# Steuerungsmodul.net
KiCad netlist of a schematic drawn in EAGLE
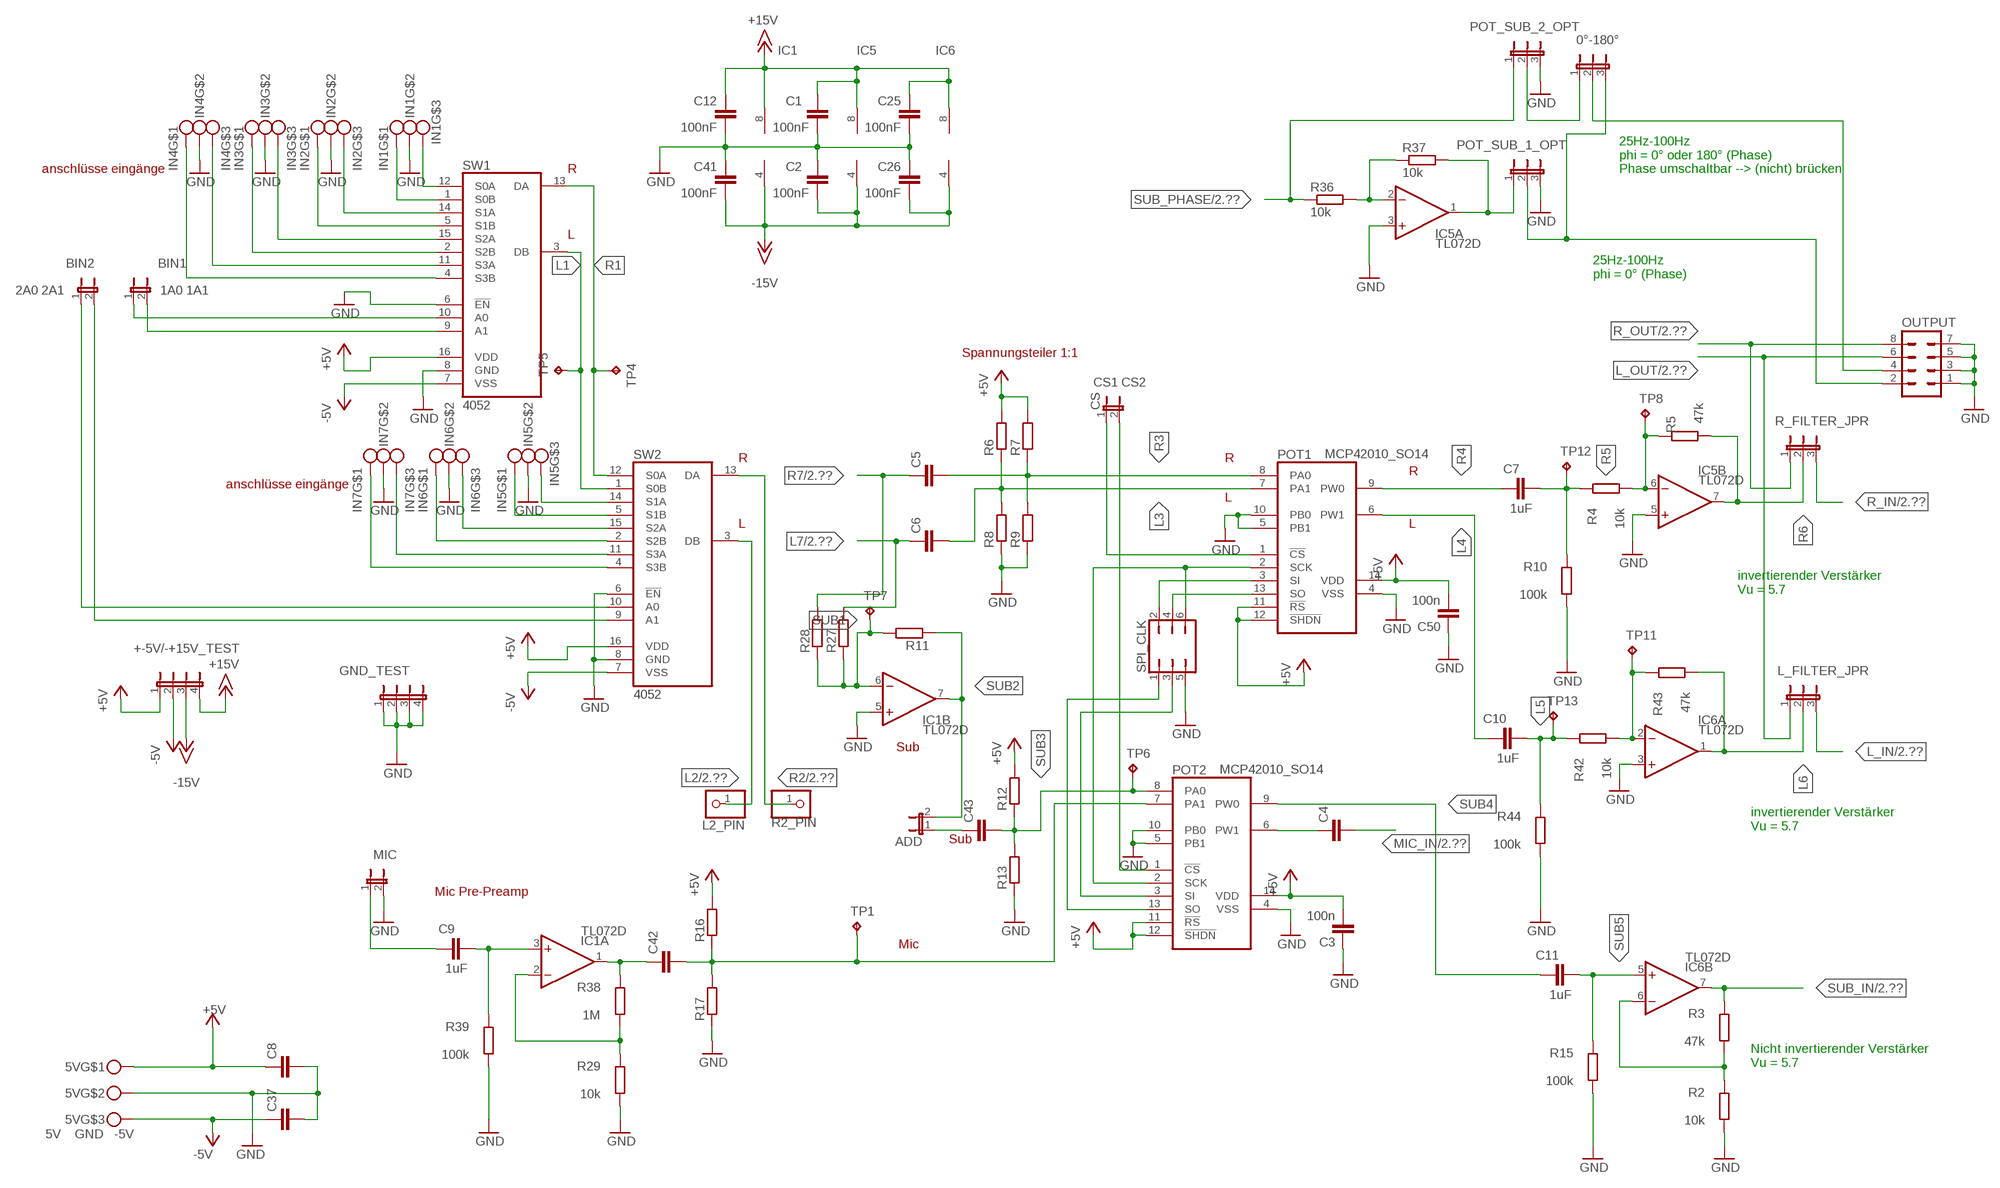
[diagram p0: schematic, sheet 1]
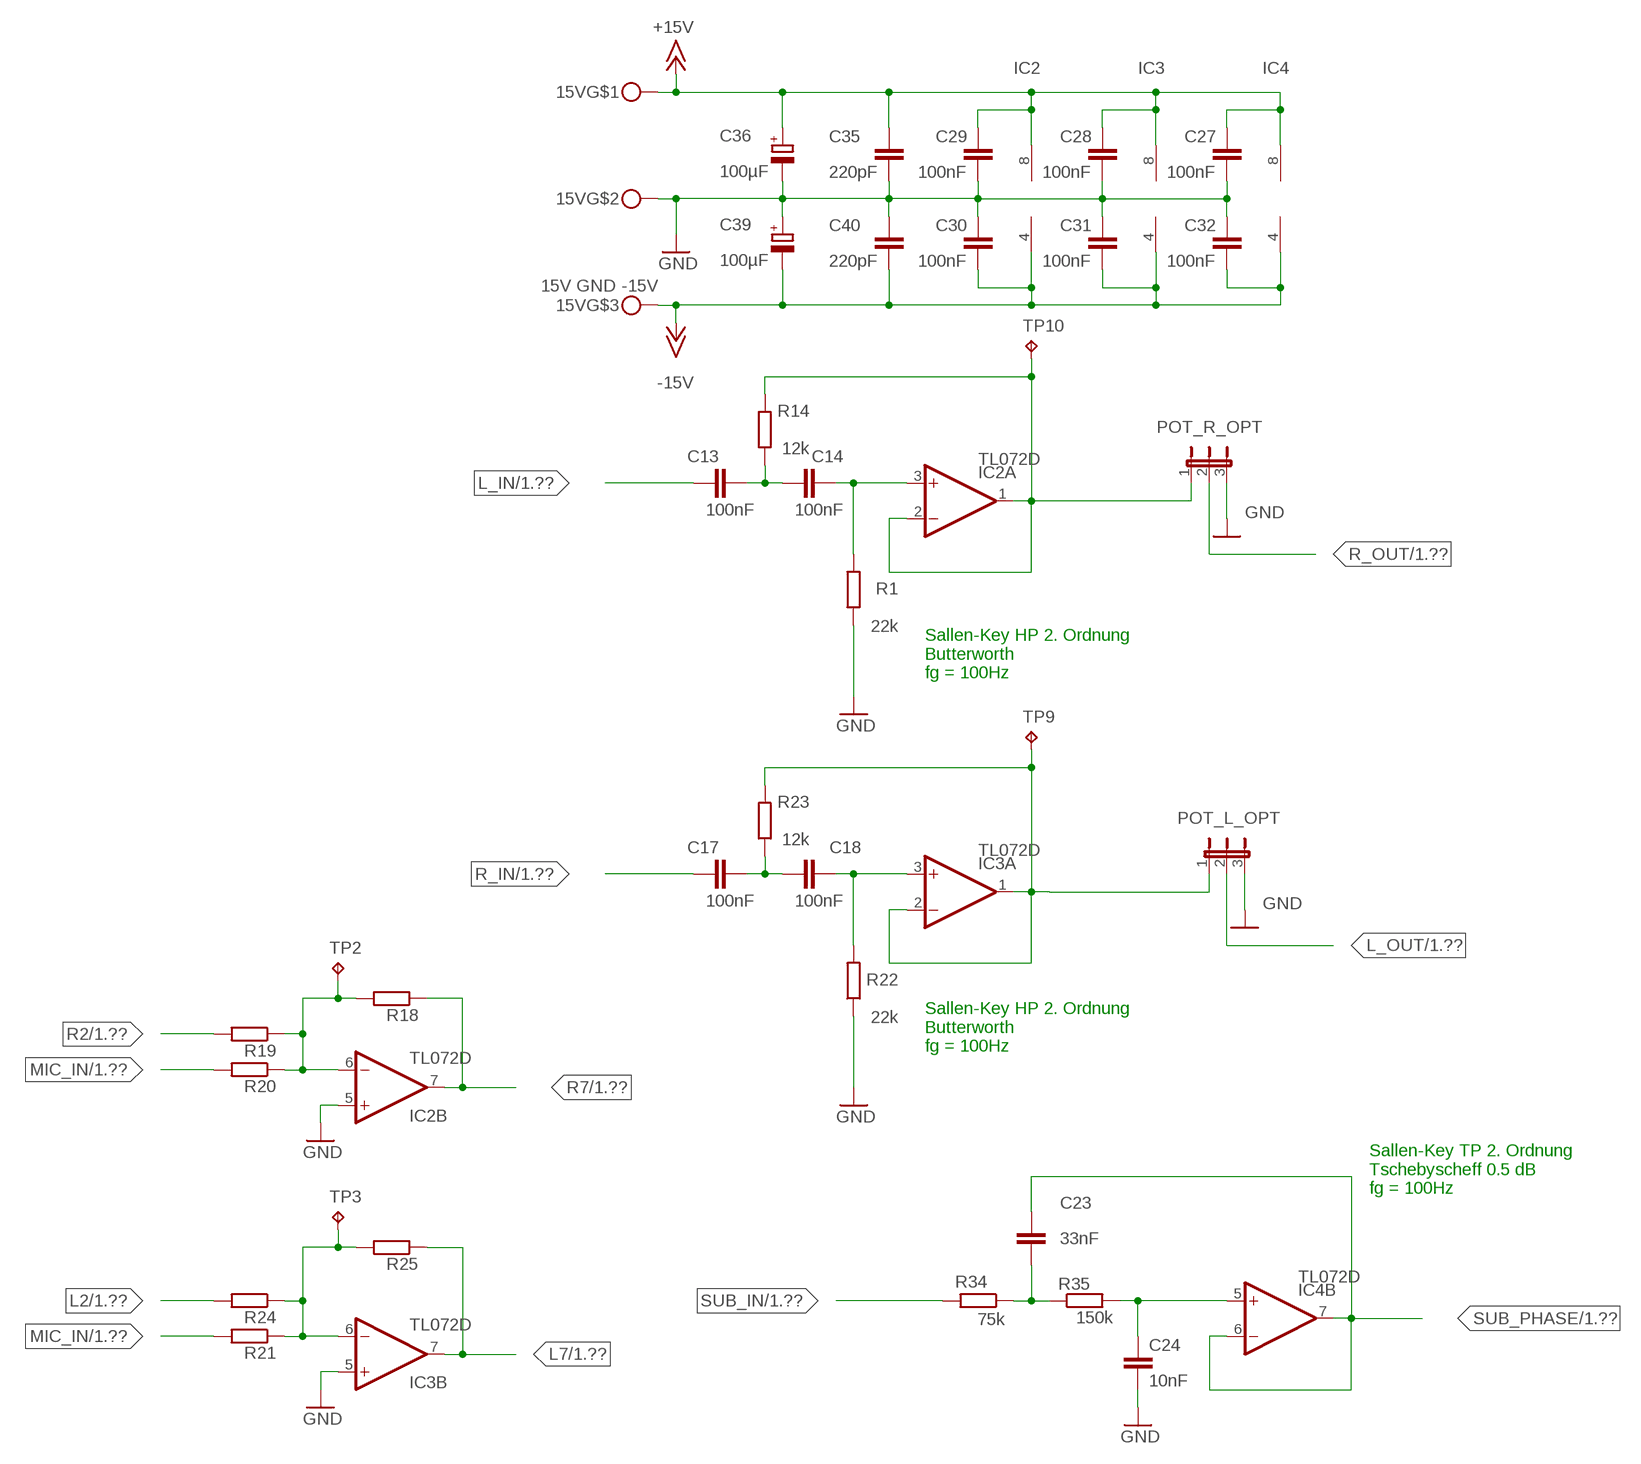
[diagram p1: schematic, sheet 2]

(export (version "E")
  (design (tool "Eeschema 10.0.6"))
  (components
    (comp (ref "+-5V/-+15V_TEST")
      (value "JP4E")
      (footprint "eagle-import:JP4")
      (libsource (lib "eagle-import") (part "JP4E"))
    )
    (comp (ref "0°-180°")
      (value "JMP3")
      (footprint "eagle-import:JMP3")
      (libsource (lib "eagle-import") (part "JMP3"))
    )
    (comp (ref "5V")
      (value "5V GND -5V")
      (footprint "eagle-import:MKDS3_3_5,08")
      (libsource (lib "eagle-import") (part "MKDS3/3_5,08"))
    )
    (comp (ref "ADD")
      (value "JMP2")
      (footprint "eagle-import:JMP2")
      (libsource (lib "eagle-import") (part "JMP2"))
    )
    (comp (ref "BIN1")
      (value "1A0 1A1")
      (footprint "eagle-import:JMP2")
      (libsource (lib "eagle-import") (part "JMP2"))
    )
    (comp (ref "BIN2")
      (value "2A0 2A1")
      (footprint "eagle-import:JMP2")
      (fields (field (name "SPICEPREFIX") "B"))
      (libsource (lib "eagle-import") (part "JMP2"))
    )
    (comp (ref "C1")
      (value "100nF")
      (footprint "eagle-import:C0805")
      (libsource (lib "eagle-import") (part "C-EUC0805"))
    )
    (comp (ref "C2")
      (value "100nF")
      (footprint "eagle-import:C0805")
      (libsource (lib "eagle-import") (part "C-EUC0805"))
    )
    (comp (ref "C3")
      (value "100n")
      (footprint "eagle-import:C0805")
      (libsource (lib "eagle-import") (part "C-EUC0805"))
    )
    (comp (ref "C4")
      (value "C-EUC0805")
      (footprint "eagle-import:C0805")
      (libsource (lib "eagle-import") (part "C-EUC0805"))
    )
    (comp (ref "C5")
      (value "C-EUC0805")
      (footprint "eagle-import:C0805")
      (libsource (lib "eagle-import") (part "C-EUC0805"))
    )
    (comp (ref "C6")
      (value "C-EUC0805")
      (footprint "eagle-import:C0805")
      (libsource (lib "eagle-import") (part "C-EUC0805"))
    )
    (comp (ref "C7")
      (value "1uF")
      (footprint "eagle-import:C025-025X050")
      (libsource (lib "eagle-import") (part "resistor_C-EU025-025X050"))
    )
    (comp (ref "C8")
      (value "C-EUC0805")
      (footprint "eagle-import:C0805")
      (libsource (lib "eagle-import") (part "C-EUC0805"))
    )
    (comp (ref "C9")
      (value "1uF")
      (footprint "eagle-import:C025-025X050")
      (libsource (lib "eagle-import") (part "resistor_C-EU025-025X050"))
    )
    (comp (ref "C10")
      (value "1uF")
      (footprint "eagle-import:C025-025X050")
      (libsource (lib "eagle-import") (part "resistor_C-EU025-025X050"))
    )
    (comp (ref "C11")
      (value "1uF")
      (footprint "eagle-import:C025-025X050")
      (libsource (lib "eagle-import") (part "resistor_C-EU025-025X050"))
    )
    (comp (ref "C12")
      (value "100nF")
      (footprint "eagle-import:C0805")
      (libsource (lib "eagle-import") (part "C-EUC0805"))
    )
    (comp (ref "C25")
      (value "100nF")
      (footprint "eagle-import:C0805")
      (libsource (lib "eagle-import") (part "C-EUC0805"))
    )
    (comp (ref "C26")
      (value "100nF")
      (footprint "eagle-import:C0805")
      (libsource (lib "eagle-import") (part "C-EUC0805"))
    )
    (comp (ref "C37")
      (value "C-EUC0805")
      (footprint "eagle-import:C0805")
      (libsource (lib "eagle-import") (part "C-EUC0805"))
    )
    (comp (ref "C41")
      (value "100nF")
      (footprint "eagle-import:C0805")
      (libsource (lib "eagle-import") (part "C-EUC0805"))
    )
    (comp (ref "C42")
      (value "C-EUC0805")
      (footprint "eagle-import:C0805")
      (libsource (lib "eagle-import") (part "C-EUC0805"))
    )
    (comp (ref "C43")
      (value "C-EUC0805")
      (footprint "eagle-import:C0805")
      (libsource (lib "eagle-import") (part "C-EUC0805"))
    )
    (comp (ref "C50")
      (value "100n")
      (footprint "eagle-import:C0805")
      (libsource (lib "eagle-import") (part "C-EUC0805"))
    )
    (comp (ref "CS")
      (value "CS1 CS2")
      (footprint "eagle-import:JMP2")
      (libsource (lib "eagle-import") (part "JMP2"))
    )
    (comp (ref "GND_TEST")
      (value "JP4E")
      (footprint "eagle-import:JP4")
      (libsource (lib "eagle-import") (part "jumper_252_JP4E"))
    )
    (comp (ref "IC1")
      (value "TL072D")
      (footprint "eagle-import:SO08")
      (libsource (lib "eagle-import") (part "TL072D"))
    )
    (comp (ref "IC5")
      (value "TL072D")
      (footprint "eagle-import:SO08")
      (libsource (lib "eagle-import") (part "TL072D"))
    )
    (comp (ref "IC6")
      (value "TL072D")
      (footprint "eagle-import:SO08")
      (libsource (lib "eagle-import") (part "TL072D"))
    )
    (comp (ref "IN1")
      (value "MKDS3/3_5,08")
      (footprint "eagle-import:MKDS3_3_5,08")
      (libsource (lib "eagle-import") (part "MKDS3/3_5,08"))
    )
    (comp (ref "IN2")
      (value "MKDS3/3_5,08")
      (footprint "eagle-import:MKDS3_3_5,08")
      (libsource (lib "eagle-import") (part "MKDS3/3_5,08"))
    )
    (comp (ref "IN3")
      (value "MKDS3/3_5,08")
      (footprint "eagle-import:MKDS3_3_5,08")
      (libsource (lib "eagle-import") (part "MKDS3/3_5,08"))
    )
    (comp (ref "IN4")
      (value "MKDS3/3_5,08")
      (footprint "eagle-import:MKDS3_3_5,08")
      (libsource (lib "eagle-import") (part "MKDS3/3_5,08"))
    )
    (comp (ref "IN5")
      (value "MKDS3/3_5,08")
      (footprint "eagle-import:MKDS3_3_5,08")
      (libsource (lib "eagle-import") (part "MKDS3/3_5,08"))
    )
    (comp (ref "IN6")
      (value "MKDS3/3_5,08")
      (footprint "eagle-import:MKDS3_3_5,08")
      (libsource (lib "eagle-import") (part "MKDS3/3_5,08"))
    )
    (comp (ref "IN7")
      (value "MKDS3/3_5,08")
      (footprint "eagle-import:MKDS3_3_5,08")
      (libsource (lib "eagle-import") (part "MKDS3/3_5,08"))
    )
    (comp (ref "L2_PIN")
      (value "PINHD-1X1")
      (footprint "eagle-import:1X01")
      (libsource (lib "eagle-import") (part "PINHD-1X1"))
    )
    (comp (ref "L_FILTER_JPR")
      (value "JMP3")
      (footprint "eagle-import:JMP3")
      (libsource (lib "eagle-import") (part "JMP3"))
    )
    (comp (ref "MIC")
      (value "JMP2")
      (footprint "eagle-import:JMP2")
      (libsource (lib "eagle-import") (part "JMP2"))
    )
    (comp (ref "OUTPUT")
      (value "MA04-2")
      (footprint "eagle-import:MA04-2")
      (libsource (lib "eagle-import") (part "MA04-2"))
    )
    (comp (ref "POT1")
      (value "MCP42010_SO14")
      (footprint "eagle-import:SO14")
      (libsource (lib "eagle-import") (part "MCP42010_SO14"))
    )
    (comp (ref "POT2")
      (value "MCP42010_SO14")
      (footprint "eagle-import:SO14")
      (libsource (lib "eagle-import") (part "MCP42010_SO14"))
    )
    (comp (ref "POT_SUB_1_OPT")
      (value "JMP3")
      (footprint "eagle-import:JMP3")
      (libsource (lib "eagle-import") (part "JMP3"))
    )
    (comp (ref "POT_SUB_2_OPT")
      (value "JMP3")
      (footprint "eagle-import:JMP3")
      (libsource (lib "eagle-import") (part "JMP3"))
    )
    (comp (ref "R2")
      (value "10k")
      (footprint "eagle-import:M0805")
      (libsource (lib "eagle-import") (part "R-EU_M0805"))
    )
    (comp (ref "R2_PIN")
      (value "PINHD-1X1")
      (footprint "eagle-import:1X01")
      (libsource (lib "eagle-import") (part "PINHD-1X1"))
    )
    (comp (ref "R3")
      (value "47k")
      (footprint "eagle-import:M0805")
      (libsource (lib "eagle-import") (part "R-EU_M0805"))
    )
    (comp (ref "R4")
      (value "10k")
      (footprint "eagle-import:M0805")
      (libsource (lib "eagle-import") (part "R-EU_M0805"))
    )
    (comp (ref "R5")
      (value "47k")
      (footprint "eagle-import:M0805")
      (libsource (lib "eagle-import") (part "R-EU_M0805"))
    )
    (comp (ref "R6")
      (value "R-EU_M0805")
      (footprint "eagle-import:M0805")
      (libsource (lib "eagle-import") (part "R-EU_M0805"))
    )
    (comp (ref "R7")
      (value "R-EU_M0805")
      (footprint "eagle-import:M0805")
      (libsource (lib "eagle-import") (part "R-EU_M0805"))
    )
    (comp (ref "R8")
      (value "R-EU_M0805")
      (footprint "eagle-import:M0805")
      (libsource (lib "eagle-import") (part "R-EU_M0805"))
    )
    (comp (ref "R9")
      (value "R-EU_M0805")
      (footprint "eagle-import:M0805")
      (libsource (lib "eagle-import") (part "R-EU_M0805"))
    )
    (comp (ref "R10")
      (value "100k")
      (footprint "eagle-import:M0805")
      (libsource (lib "eagle-import") (part "R-EU_M0805"))
    )
    (comp (ref "R11")
      (value "R-EU_M0805")
      (footprint "eagle-import:M0805")
      (libsource (lib "eagle-import") (part "R-EU_M0805"))
    )
    (comp (ref "R12")
      (value "R-EU_M0805")
      (footprint "eagle-import:M0805")
      (libsource (lib "eagle-import") (part "R-EU_M0805"))
    )
    (comp (ref "R13")
      (value "R-EU_M0805")
      (footprint "eagle-import:M0805")
      (libsource (lib "eagle-import") (part "R-EU_M0805"))
    )
    (comp (ref "R15")
      (value "100k")
      (footprint "eagle-import:M0805")
      (libsource (lib "eagle-import") (part "R-EU_M0805"))
    )
    (comp (ref "R16")
      (value "R-EU_M0805")
      (footprint "eagle-import:M0805")
      (libsource (lib "eagle-import") (part "R-EU_M0805"))
    )
    (comp (ref "R17")
      (value "R-EU_M0805")
      (footprint "eagle-import:M0805")
      (libsource (lib "eagle-import") (part "R-EU_M0805"))
    )
    (comp (ref "R27")
      (value "R-EU_M0805")
      (footprint "eagle-import:M0805")
      (libsource (lib "eagle-import") (part "R-EU_M0805"))
    )
    (comp (ref "R28")
      (value "R-EU_M0805")
      (footprint "eagle-import:M0805")
      (libsource (lib "eagle-import") (part "R-EU_M0805"))
    )
    (comp (ref "R29")
      (value "10k")
      (footprint "eagle-import:M0805")
      (libsource (lib "eagle-import") (part "R-EU_M0805"))
    )
    (comp (ref "R36")
      (value "10k")
      (footprint "eagle-import:M0805")
      (libsource (lib "eagle-import") (part "R-EU_M0805"))
    )
    (comp (ref "R37")
      (value "10k")
      (footprint "eagle-import:M0805")
      (libsource (lib "eagle-import") (part "R-EU_M0805"))
    )
    (comp (ref "R38")
      (value "1M")
      (footprint "eagle-import:M0805")
      (libsource (lib "eagle-import") (part "R-EU_M0805"))
    )
    (comp (ref "R39")
      (value "100k")
      (footprint "eagle-import:M0805")
      (libsource (lib "eagle-import") (part "R-EU_M0805"))
    )
    (comp (ref "R42")
      (value "10k")
      (footprint "eagle-import:M0805")
      (libsource (lib "eagle-import") (part "R-EU_M0805"))
    )
    (comp (ref "R43")
      (value "47k")
      (footprint "eagle-import:M0805")
      (libsource (lib "eagle-import") (part "R-EU_M0805"))
    )
    (comp (ref "R44")
      (value "100k")
      (footprint "eagle-import:M0805")
      (libsource (lib "eagle-import") (part "R-EU_M0805"))
    )
    (comp (ref "R_FILTER_JPR")
      (value "JMP3")
      (footprint "eagle-import:JMP3")
      (libsource (lib "eagle-import") (part "JMP3"))
    )
    (comp (ref "SPI_CLK")
      (value "JP3Q")
      (footprint "eagle-import:JP3Q")
      (libsource (lib "eagle-import") (part "JP3Q"))
    )
    (comp (ref "SW1")
      (value "4052")
      (footprint "eagle-import:SO-16")
      (libsource (lib "eagle-import") (part "5042_SO16_NEU"))
    )
    (comp (ref "SW2")
      (value "4052")
      (footprint "eagle-import:SO-16")
      (libsource (lib "eagle-import") (part "5042_SO16_NEU"))
    )
    (comp (ref "TP1")
      (value "TPB2,54")
      (footprint "eagle-import:B2,54")
      (libsource (lib "eagle-import") (part "TPB2,54"))
    )
    (comp (ref "TP4")
      (value "TPB2,54")
      (footprint "eagle-import:B2,54")
      (libsource (lib "eagle-import") (part "TPB2,54"))
    )
    (comp (ref "TP5")
      (value "TPB2,54")
      (footprint "eagle-import:B2,54")
      (libsource (lib "eagle-import") (part "TPB2,54"))
    )
    (comp (ref "TP6")
      (value "TPB2,54")
      (footprint "eagle-import:B2,54")
      (libsource (lib "eagle-import") (part "TPB2,54"))
    )
    (comp (ref "TP7")
      (value "TPB2,54")
      (footprint "eagle-import:B2,54")
      (libsource (lib "eagle-import") (part "TPB2,54"))
    )
    (comp (ref "TP8")
      (value "TPB2,54")
      (footprint "eagle-import:B2,54")
      (libsource (lib "eagle-import") (part "TPB2,54"))
    )
    (comp (ref "TP11")
      (value "TPB2,54")
      (footprint "eagle-import:B2,54")
      (libsource (lib "eagle-import") (part "TPB2,54"))
    )
    (comp (ref "TP12")
      (value "TPB2,54")
      (footprint "eagle-import:B2,54")
      (libsource (lib "eagle-import") (part "TPB2,54"))
    )
    (comp (ref "TP13")
      (value "TPB2,54")
      (footprint "eagle-import:B2,54")
      (libsource (lib "eagle-import") (part "TPB2,54"))
    )
    (comp (ref "15V")
      (value "15V GND -15V")
      (footprint "eagle-import:MKDS3_3_5,08")
      (libsource (lib "eagle-import") (part "MKDS3/3_5,08"))
    )
    (comp (ref "C13")
      (value "100nF")
      (footprint "eagle-import:C0805")
      (libsource (lib "eagle-import") (part "C-EUC0805"))
    )
    (comp (ref "C14")
      (value "100nF")
      (footprint "eagle-import:C0805")
      (libsource (lib "eagle-import") (part "C-EUC0805"))
    )
    (comp (ref "C17")
      (value "100nF")
      (footprint "eagle-import:C0805")
      (libsource (lib "eagle-import") (part "C-EUC0805"))
    )
    (comp (ref "C18")
      (value "100nF")
      (footprint "eagle-import:C0805")
      (libsource (lib "eagle-import") (part "C-EUC0805"))
    )
    (comp (ref "C23")
      (value "33nF")
      (footprint "eagle-import:C0805")
      (libsource (lib "eagle-import") (part "C-EUC0805"))
    )
    (comp (ref "C24")
      (value "10nF")
      (footprint "eagle-import:C0805")
      (libsource (lib "eagle-import") (part "C-EUC0805"))
    )
    (comp (ref "C27")
      (value "100nF")
      (footprint "eagle-import:C0805")
      (libsource (lib "eagle-import") (part "C-EUC0805"))
    )
    (comp (ref "C28")
      (value "100nF")
      (footprint "eagle-import:C0805")
      (libsource (lib "eagle-import") (part "C-EUC0805"))
    )
    (comp (ref "C29")
      (value "100nF")
      (footprint "eagle-import:C0805")
      (libsource (lib "eagle-import") (part "C-EUC0805"))
    )
    (comp (ref "C30")
      (value "100nF")
      (footprint "eagle-import:C0805")
      (libsource (lib "eagle-import") (part "C-EUC0805"))
    )
    (comp (ref "C31")
      (value "100nF")
      (footprint "eagle-import:C0805")
      (libsource (lib "eagle-import") (part "C-EUC0805"))
    )
    (comp (ref "C32")
      (value "100nF")
      (footprint "eagle-import:C0805")
      (libsource (lib "eagle-import") (part "C-EUC0805"))
    )
    (comp (ref "C35")
      (value "220pF")
      (footprint "eagle-import:C0805")
      (libsource (lib "eagle-import") (part "C-EUC0805"))
    )
    (comp (ref "C36")
      (value "100µF")
      (footprint "eagle-import:E2,5-6")
      (libsource (lib "eagle-import") (part "CPOL-EUE2.5-6"))
    )
    (comp (ref "C39")
      (value "100µF")
      (footprint "eagle-import:E2,5-6")
      (libsource (lib "eagle-import") (part "CPOL-EUE2.5-6"))
    )
    (comp (ref "C40")
      (value "220pF")
      (footprint "eagle-import:C0805")
      (libsource (lib "eagle-import") (part "C-EUC0805"))
    )
    (comp (ref "IC2")
      (value "TL072D")
      (footprint "eagle-import:SO08")
      (libsource (lib "eagle-import") (part "TL072D"))
    )
    (comp (ref "IC3")
      (value "TL072D")
      (footprint "eagle-import:SO08")
      (libsource (lib "eagle-import") (part "TL072D"))
    )
    (comp (ref "IC4")
      (value "TL072D")
      (footprint "eagle-import:SO08")
      (libsource (lib "eagle-import") (part "TL072D"))
    )
    (comp (ref "POT_L_OPT")
      (value "JMP3")
      (footprint "eagle-import:JMP3")
      (libsource (lib "eagle-import") (part "JMP3"))
    )
    (comp (ref "POT_R_OPT")
      (value "JMP3")
      (footprint "eagle-import:JMP3")
      (libsource (lib "eagle-import") (part "JMP3"))
    )
    (comp (ref "R1")
      (value "22k")
      (footprint "eagle-import:M0805")
      (libsource (lib "eagle-import") (part "R-EU_M0805"))
    )
    (comp (ref "R14")
      (value "12k")
      (footprint "eagle-import:M0805")
      (libsource (lib "eagle-import") (part "R-EU_M0805"))
    )
    (comp (ref "R18")
      (value "R-EU_M0805")
      (footprint "eagle-import:M0805")
      (libsource (lib "eagle-import") (part "R-EU_M0805"))
    )
    (comp (ref "R19")
      (value "R-EU_M0805")
      (footprint "eagle-import:M0805")
      (libsource (lib "eagle-import") (part "R-EU_M0805"))
    )
    (comp (ref "R20")
      (value "R-EU_M0805")
      (footprint "eagle-import:M0805")
      (libsource (lib "eagle-import") (part "R-EU_M0805"))
    )
    (comp (ref "R21")
      (value "R-EU_M0805")
      (footprint "eagle-import:M0805")
      (libsource (lib "eagle-import") (part "R-EU_M0805"))
    )
    (comp (ref "R22")
      (value "22k")
      (footprint "eagle-import:M0805")
      (libsource (lib "eagle-import") (part "R-EU_M0805"))
    )
    (comp (ref "R23")
      (value "12k")
      (footprint "eagle-import:M0805")
      (libsource (lib "eagle-import") (part "R-EU_M0805"))
    )
    (comp (ref "R24")
      (value "R-EU_M0805")
      (footprint "eagle-import:M0805")
      (libsource (lib "eagle-import") (part "R-EU_M0805"))
    )
    (comp (ref "R25")
      (value "R-EU_M0805")
      (footprint "eagle-import:M0805")
      (libsource (lib "eagle-import") (part "R-EU_M0805"))
    )
    (comp (ref "R34")
      (value "75k")
      (footprint "eagle-import:M0805")
      (libsource (lib "eagle-import") (part "R-EU_M0805"))
    )
    (comp (ref "R35")
      (value "150k")
      (footprint "eagle-import:M0805")
      (libsource (lib "eagle-import") (part "R-EU_M0805"))
    )
    (comp (ref "TP2")
      (value "TPB2,54")
      (footprint "eagle-import:B2,54")
      (libsource (lib "eagle-import") (part "TPB2,54"))
    )
    (comp (ref "TP3")
      (value "TPB2,54")
      (footprint "eagle-import:B2,54")
      (libsource (lib "eagle-import") (part "TPB2,54"))
    )
    (comp (ref "TP9")
      (value "TPB2,54")
      (footprint "eagle-import:B2,54")
      (libsource (lib "eagle-import") (part "TPB2,54"))
    )
    (comp (ref "TP10")
      (value "TPB2,54")
      (footprint "eagle-import:B2,54")
      (libsource (lib "eagle-import") (part "TPB2,54"))
    )
  )
  (nets
    (net (code "1") (name "+5V") (class "Default")
      (node (ref "+-5V/-+15V_TEST") (pin "1") (pinfunction "1_1") (pintype "passive"))
      (node (ref "5V") (pin "P$1") (pinfunction "KL_P$1") (pintype "passive"))
      (node (ref "C3") (pin "2") (pinfunction "2_2") (pintype "passive"))
      (node (ref "C50") (pin "2") (pinfunction "2_2") (pintype "passive"))
      (node (ref "C8") (pin "1") (pinfunction "1_1") (pintype "passive"))
      (node (ref "POT1") (pin "11") (pinfunction "~{RS}_11") (pintype "bidirectional"))
      (node (ref "POT1") (pin "12") (pinfunction "~{SHDN}_12") (pintype "bidirectional"))
      (node (ref "POT1") (pin "14") (pinfunction "VDD_14") (pintype "input"))
      (node (ref "POT2") (pin "11") (pinfunction "~{RS}_11") (pintype "bidirectional"))
      (node (ref "POT2") (pin "12") (pinfunction "~{SHDN}_12") (pintype "bidirectional"))
      (node (ref "POT2") (pin "14") (pinfunction "VDD_14") (pintype "input"))
      (node (ref "R12") (pin "2") (pinfunction "2_2") (pintype "passive"))
      (node (ref "R16") (pin "2") (pinfunction "2_2") (pintype "passive"))
      (node (ref "R6") (pin "2") (pinfunction "2_2") (pintype "passive"))
      (node (ref "R7") (pin "2") (pinfunction "2_2") (pintype "passive"))
      (node (ref "SW1") (pin "16") (pinfunction "VDD_16") (pintype "bidirectional"))
      (node (ref "SW2") (pin "16") (pinfunction "VDD_16") (pintype "bidirectional"))
    )
    (net (code "2") (name "+15V") (class "Default")
      (node (ref "+-5V/-+15V_TEST") (pin "4") (pinfunction "4_4") (pintype "passive"))
      (node (ref "15V") (pin "P$1") (pinfunction "KL_P$1") (pintype "passive"))
      (node (ref "C1") (pin "1") (pinfunction "1_1") (pintype "passive"))
      (node (ref "C12") (pin "1") (pinfunction "1_1") (pintype "passive"))
      (node (ref "C25") (pin "1") (pinfunction "1_1") (pintype "passive"))
      (node (ref "C27") (pin "1") (pinfunction "1_1") (pintype "passive"))
      (node (ref "C28") (pin "1") (pinfunction "1_1") (pintype "passive"))
      (node (ref "C29") (pin "1") (pinfunction "1_1") (pintype "passive"))
      (node (ref "C35") (pin "1") (pinfunction "1_1") (pintype "passive"))
      (node (ref "C36") (pin "+") (pinfunction "+_+") (pintype "passive"))
      (node (ref "IC1") (pin "8") (pinfunction "V+_8") (pintype "power_in"))
      (node (ref "IC2") (pin "8") (pinfunction "V+_8") (pintype "power_in"))
      (node (ref "IC3") (pin "8") (pinfunction "V+_8") (pintype "power_in"))
      (node (ref "IC4") (pin "8") (pinfunction "V+_8") (pintype "power_in"))
      (node (ref "IC5") (pin "8") (pinfunction "V+_8") (pintype "power_in"))
      (node (ref "IC6") (pin "8") (pinfunction "V+_8") (pintype "power_in"))
    )
    (net (code "3") (name "-5V") (class "Default")
      (node (ref "+-5V/-+15V_TEST") (pin "2") (pinfunction "2_2") (pintype "passive"))
      (node (ref "5V") (pin "P$3") (pinfunction "KL_P$3") (pintype "passive"))
      (node (ref "C37") (pin "1") (pinfunction "1_1") (pintype "passive"))
      (node (ref "SW1") (pin "7") (pinfunction "VSS_7") (pintype "bidirectional"))
      (node (ref "SW2") (pin "7") (pinfunction "VSS_7") (pintype "bidirectional"))
    )
    (net (code "4") (name "-15V") (class "Default")
      (node (ref "+-5V/-+15V_TEST") (pin "3") (pinfunction "3_3") (pintype "passive"))
      (node (ref "15V") (pin "P$3") (pinfunction "KL_P$3") (pintype "passive"))
      (node (ref "C2") (pin "2") (pinfunction "2_2") (pintype "passive"))
      (node (ref "C26") (pin "2") (pinfunction "2_2") (pintype "passive"))
      (node (ref "C30") (pin "2") (pinfunction "2_2") (pintype "passive"))
      (node (ref "C31") (pin "2") (pinfunction "2_2") (pintype "passive"))
      (node (ref "C32") (pin "2") (pinfunction "2_2") (pintype "passive"))
      (node (ref "C39") (pin "-") (pinfunction "-_-") (pintype "passive"))
      (node (ref "C40") (pin "2") (pinfunction "2_2") (pintype "passive"))
      (node (ref "C41") (pin "2") (pinfunction "2_2") (pintype "passive"))
      (node (ref "IC1") (pin "4") (pinfunction "V-_4") (pintype "power_in"))
      (node (ref "IC2") (pin "4") (pinfunction "V-_4") (pintype "power_in"))
      (node (ref "IC3") (pin "4") (pinfunction "V-_4") (pintype "power_in"))
      (node (ref "IC4") (pin "4") (pinfunction "V-_4") (pintype "power_in"))
      (node (ref "IC5") (pin "4") (pinfunction "V-_4") (pintype "power_in"))
      (node (ref "IC6") (pin "4") (pinfunction "V-_4") (pintype "power_in"))
    )
    (net (code "5") (name "GND") (class "Default")
      (node (ref "15V") (pin "P$2") (pinfunction "KL_P$2") (pintype "passive"))
      (node (ref "5V") (pin "P$2") (pinfunction "KL_P$2") (pintype "passive"))
      (node (ref "C1") (pin "2") (pinfunction "2_2") (pintype "passive"))
      (node (ref "C12") (pin "2") (pinfunction "2_2") (pintype "passive"))
      (node (ref "C2") (pin "1") (pinfunction "1_1") (pintype "passive"))
      (node (ref "C24") (pin "2") (pinfunction "2_2") (pintype "passive"))
      (node (ref "C25") (pin "2") (pinfunction "2_2") (pintype "passive"))
      (node (ref "C26") (pin "1") (pinfunction "1_1") (pintype "passive"))
      (node (ref "C27") (pin "2") (pinfunction "2_2") (pintype "passive"))
      (node (ref "C28") (pin "2") (pinfunction "2_2") (pintype "passive"))
      (node (ref "C29") (pin "2") (pinfunction "2_2") (pintype "passive"))
      (node (ref "C3") (pin "1") (pinfunction "1_1") (pintype "passive"))
      (node (ref "C30") (pin "1") (pinfunction "1_1") (pintype "passive"))
      (node (ref "C31") (pin "1") (pinfunction "1_1") (pintype "passive"))
      (node (ref "C32") (pin "1") (pinfunction "1_1") (pintype "passive"))
      (node (ref "C35") (pin "2") (pinfunction "2_2") (pintype "passive"))
      (node (ref "C36") (pin "-") (pinfunction "-_-") (pintype "passive"))
      (node (ref "C37") (pin "2") (pinfunction "2_2") (pintype "passive"))
      (node (ref "C39") (pin "+") (pinfunction "+_+") (pintype "passive"))
      (node (ref "C40") (pin "1") (pinfunction "1_1") (pintype "passive"))
      (node (ref "C41") (pin "1") (pinfunction "1_1") (pintype "passive"))
      (node (ref "C50") (pin "1") (pinfunction "1_1") (pintype "passive"))
      (node (ref "C8") (pin "2") (pinfunction "2_2") (pintype "passive"))
      (node (ref "GND_TEST") (pin "1") (pinfunction "1_1") (pintype "passive"))
      (node (ref "GND_TEST") (pin "2") (pinfunction "2_2") (pintype "passive"))
      (node (ref "GND_TEST") (pin "3") (pinfunction "3_3") (pintype "passive"))
      (node (ref "GND_TEST") (pin "4") (pinfunction "4_4") (pintype "passive"))
      (node (ref "IC1") (pin "5") (pinfunction "+IN_5") (pintype "input"))
      (node (ref "IC2") (pin "5") (pinfunction "+IN_5") (pintype "input"))
      (node (ref "IC3") (pin "5") (pinfunction "+IN_5") (pintype "input"))
      (node (ref "IC5") (pin "3") (pinfunction "+IN_3") (pintype "input"))
      (node (ref "IC5") (pin "5") (pinfunction "+IN_5") (pintype "input"))
      (node (ref "IC6") (pin "3") (pinfunction "+IN_3") (pintype "input"))
      (node (ref "IN1") (pin "P$2") (pinfunction "KL_P$2") (pintype "passive"))
      (node (ref "IN2") (pin "P$2") (pinfunction "KL_P$2") (pintype "passive"))
      (node (ref "IN3") (pin "P$2") (pinfunction "KL_P$2") (pintype "passive"))
      (node (ref "IN4") (pin "P$2") (pinfunction "KL_P$2") (pintype "passive"))
      (node (ref "IN5") (pin "P$2") (pinfunction "KL_P$2") (pintype "passive"))
      (node (ref "IN6") (pin "P$2") (pinfunction "KL_P$2") (pintype "passive"))
      (node (ref "IN7") (pin "P$2") (pinfunction "KL_P$2") (pintype "passive"))
      (node (ref "MIC") (pin "2") (pinfunction "2_2") (pintype "passive"))
      (node (ref "OUTPUT") (pin "1") (pinfunction "1_1") (pintype "passive"))
      (node (ref "OUTPUT") (pin "3") (pinfunction "3_3") (pintype "passive"))
      (node (ref "OUTPUT") (pin "5") (pinfunction "5_5") (pintype "passive"))
      (node (ref "OUTPUT") (pin "7") (pinfunction "7_7") (pintype "passive"))
      (node (ref "POT1") (pin "10") (pinfunction "PB0_10") (pintype "bidirectional"))
      (node (ref "POT1") (pin "4") (pinfunction "VSS_4") (pintype "input"))
      (node (ref "POT1") (pin "5") (pinfunction "PB1_5") (pintype "bidirectional"))
      (node (ref "POT2") (pin "10") (pinfunction "PB0_10") (pintype "bidirectional"))
      (node (ref "POT2") (pin "4") (pinfunction "VSS_4") (pintype "input"))
      (node (ref "POT2") (pin "5") (pinfunction "PB1_5") (pintype "bidirectional"))
      (node (ref "POT_L_OPT") (pin "3") (pinfunction "3_3") (pintype "passive"))
      (node (ref "POT_R_OPT") (pin "3") (pinfunction "3_3") (pintype "passive"))
      (node (ref "POT_SUB_1_OPT") (pin "3") (pinfunction "3_3") (pintype "passive"))
      (node (ref "POT_SUB_2_OPT") (pin "3") (pinfunction "3_3") (pintype "passive"))
      (node (ref "R1") (pin "1") (pinfunction "1_1") (pintype "passive"))
      (node (ref "R10") (pin "1") (pinfunction "1_1") (pintype "passive"))
      (node (ref "R13") (pin "1") (pinfunction "1_1") (pintype "passive"))
      (node (ref "R15") (pin "1") (pinfunction "1_1") (pintype "passive"))
      (node (ref "R17") (pin "1") (pinfunction "1_1") (pintype "passive"))
      (node (ref "R2") (pin "1") (pinfunction "1_1") (pintype "passive"))
      (node (ref "R22") (pin "1") (pinfunction "1_1") (pintype "passive"))
      (node (ref "R29") (pin "1") (pinfunction "1_1") (pintype "passive"))
      (node (ref "R39") (pin "1") (pinfunction "1_1") (pintype "passive"))
      (node (ref "R44") (pin "1") (pinfunction "1_1") (pintype "passive"))
      (node (ref "R8") (pin "1") (pinfunction "1_1") (pintype "passive"))
      (node (ref "R9") (pin "1") (pinfunction "1_1") (pintype "passive"))
      (node (ref "SPI_CLK") (pin "5") (pinfunction "5_5") (pintype "passive"))
      (node (ref "SW1") (pin "6") (pinfunction "~{EN}_6") (pintype "input"))
      (node (ref "SW1") (pin "8") (pinfunction "GND_8") (pintype "bidirectional"))
      (node (ref "SW2") (pin "6") (pinfunction "~{EN}_6") (pintype "input"))
      (node (ref "SW2") (pin "8") (pinfunction "GND_8") (pintype "bidirectional"))
    )
    (net (code "6") (name "L1") (class "Default")
      (node (ref "SW1") (pin "3") (pinfunction "DB_3") (pintype "bidirectional"))
      (node (ref "SW2") (pin "1") (pinfunction "S0B_1") (pintype "bidirectional"))
      (node (ref "TP5") (pin "TP") (pinfunction "TP_TP") (pintype "input"))
    )
    (net (code "7") (name "L2") (class "Default")
      (node (ref "L2_PIN") (pin "1") (pinfunction "1_1") (pintype "passive"))
      (node (ref "R24") (pin "2") (pinfunction "2_2") (pintype "passive"))
      (node (ref "SW2") (pin "3") (pinfunction "DB_3") (pintype "bidirectional"))
    )
    (net (code "8") (name "L3") (class "Default")
      (node (ref "C6") (pin "2") (pinfunction "2_2") (pintype "passive"))
      (node (ref "POT1") (pin "7") (pinfunction "PA1_7") (pintype "bidirectional"))
      (node (ref "R6") (pin "1") (pinfunction "1_1") (pintype "passive"))
      (node (ref "R8") (pin "2") (pinfunction "2_2") (pintype "passive"))
    )
    (net (code "9") (name "L4") (class "Default")
      (node (ref "C10") (pin "1") (pinfunction "1_1") (pintype "passive"))
      (node (ref "POT1") (pin "6") (pinfunction "PW1_6") (pintype "bidirectional"))
    )
    (net (code "10") (name "L5") (class "Default")
      (node (ref "C10") (pin "2") (pinfunction "2_2") (pintype "passive"))
      (node (ref "R42") (pin "2") (pinfunction "2_2") (pintype "passive"))
      (node (ref "R44") (pin "2") (pinfunction "2_2") (pintype "passive"))
      (node (ref "TP13") (pin "TP") (pinfunction "TP_TP") (pintype "input"))
    )
    (net (code "11") (name "L6") (class "Default")
      (node (ref "IC6") (pin "1") (pinfunction "OUT_1") (pintype "output"))
      (node (ref "L_FILTER_JPR") (pin "2") (pinfunction "2_2") (pintype "passive"))
      (node (ref "R43") (pin "1") (pinfunction "1_1") (pintype "passive"))
    )
    (net (code "12") (name "L7") (class "Default")
      (node (ref "C6") (pin "1") (pinfunction "1_1") (pintype "passive"))
      (node (ref "IC3") (pin "7") (pinfunction "OUT_7") (pintype "output"))
      (node (ref "R25") (pin "1") (pinfunction "1_1") (pintype "passive"))
      (node (ref "R27") (pin "2") (pinfunction "2_2") (pintype "passive"))
    )
    (net (code "13") (name "L_IN") (class "Default")
      (node (ref "C13") (pin "1") (pinfunction "1_1") (pintype "passive"))
      (node (ref "L_FILTER_JPR") (pin "3") (pinfunction "3_3") (pintype "passive"))
    )
    (net (code "14") (name "L_OUT") (class "Default")
      (node (ref "L_FILTER_JPR") (pin "1") (pinfunction "1_1") (pintype "passive"))
      (node (ref "OUTPUT") (pin "6") (pinfunction "6_6") (pintype "passive"))
      (node (ref "POT_L_OPT") (pin "2") (pinfunction "2_2") (pintype "passive"))
    )
    (net (code "15") (name "MIC_IN") (class "Default")
      (node (ref "C4") (pin "2") (pinfunction "2_2") (pintype "passive"))
      (node (ref "R20") (pin "2") (pinfunction "2_2") (pintype "passive"))
      (node (ref "R21") (pin "2") (pinfunction "2_2") (pintype "passive"))
    )
    (net (code "16") (name "Net-(0°-180°-Pad1)") (class "Default")
      (node (ref "0°-180°") (pin "1") (pinfunction "1_1") (pintype "passive"))
      (node (ref "POT_SUB_2_OPT") (pin "2") (pinfunction "2_2") (pintype "passive"))
    )
    (net (code "17") (name "Net-(0°-180°-Pad2)") (class "Default")
      (node (ref "0°-180°") (pin "2") (pinfunction "2_2") (pintype "passive"))
      (node (ref "OUTPUT") (pin "4") (pinfunction "4_4") (pintype "passive"))
    )
    (net (code "18") (name "Net-(0°-180°-Pad3)") (class "Default")
      (node (ref "0°-180°") (pin "3") (pinfunction "3_3") (pintype "passive"))
      (node (ref "OUTPUT") (pin "2") (pinfunction "2_2") (pintype "passive"))
      (node (ref "POT_SUB_1_OPT") (pin "2") (pinfunction "2_2") (pintype "passive"))
    )
    (net (code "19") (name "Net-(ADD-Pad1)") (class "Default")
      (node (ref "ADD") (pin "1") (pinfunction "1_1") (pintype "passive"))
      (node (ref "C43") (pin "1") (pinfunction "1_1") (pintype "passive"))
    )
    (net (code "20") (name "Net-(C9-Pad1)") (class "Default")
      (node (ref "C9") (pin "1") (pinfunction "1_1") (pintype "passive"))
      (node (ref "MIC") (pin "1") (pinfunction "1_1") (pintype "passive"))
    )
    (net (code "21") (name "Net-(C13-Pad2)") (class "Default")
      (node (ref "C13") (pin "2") (pinfunction "2_2") (pintype "passive"))
      (node (ref "C14") (pin "1") (pinfunction "1_1") (pintype "passive"))
      (node (ref "R14") (pin "1") (pinfunction "1_1") (pintype "passive"))
    )
    (net (code "22") (name "Net-(C17-Pad2)") (class "Default")
      (node (ref "C17") (pin "2") (pinfunction "2_2") (pintype "passive"))
      (node (ref "C18") (pin "1") (pinfunction "1_1") (pintype "passive"))
      (node (ref "R23") (pin "1") (pinfunction "1_1") (pintype "passive"))
    )
    (net (code "23") (name "Net-(C23-Pad2)") (class "Default")
      (node (ref "C23") (pin "2") (pinfunction "2_2") (pintype "passive"))
      (node (ref "R34") (pin "1") (pinfunction "1_1") (pintype "passive"))
      (node (ref "R35") (pin "1") (pinfunction "1_1") (pintype "passive"))
    )
    (net (code "24") (name "Net-(IC1A-+IN)") (class "Default")
      (node (ref "C9") (pin "2") (pinfunction "2_2") (pintype "passive"))
      (node (ref "IC1") (pin "3") (pinfunction "+IN_3") (pintype "input"))
      (node (ref "R39") (pin "2") (pinfunction "2_2") (pintype "passive"))
    )
    (net (code "25") (name "Net-(IC1A--IN)") (class "Default")
      (node (ref "IC1") (pin "2") (pinfunction "-IN_2") (pintype "input"))
      (node (ref "R29") (pin "2") (pinfunction "2_2") (pintype "passive"))
      (node (ref "R38") (pin "1") (pinfunction "1_1") (pintype "passive"))
    )
    (net (code "26") (name "Net-(IC1A-OUT)") (class "Default")
      (node (ref "C42") (pin "1") (pinfunction "1_1") (pintype "passive"))
      (node (ref "IC1") (pin "1") (pinfunction "OUT_1") (pintype "output"))
      (node (ref "R38") (pin "2") (pinfunction "2_2") (pintype "passive"))
    )
    (net (code "27") (name "Net-(IC2A-+IN)") (class "Default")
      (node (ref "C14") (pin "2") (pinfunction "2_2") (pintype "passive"))
      (node (ref "IC2") (pin "3") (pinfunction "+IN_3") (pintype "input"))
      (node (ref "R1") (pin "2") (pinfunction "2_2") (pintype "passive"))
    )
    (net (code "28") (name "Net-(IC2A--IN)") (class "Default")
      (node (ref "IC2") (pin "1") (pinfunction "OUT_1") (pintype "output"))
      (node (ref "IC2") (pin "2") (pinfunction "-IN_2") (pintype "input"))
      (node (ref "POT_R_OPT") (pin "1") (pinfunction "1_1") (pintype "passive"))
      (node (ref "R14") (pin "2") (pinfunction "2_2") (pintype "passive"))
      (node (ref "TP10") (pin "TP") (pinfunction "TP_TP") (pintype "input"))
    )
    (net (code "29") (name "Net-(IC2B--IN)") (class "Default")
      (node (ref "IC2") (pin "6") (pinfunction "-IN_6") (pintype "input"))
      (node (ref "R18") (pin "2") (pinfunction "2_2") (pintype "passive"))
      (node (ref "R19") (pin "1") (pinfunction "1_1") (pintype "passive"))
      (node (ref "R20") (pin "1") (pinfunction "1_1") (pintype "passive"))
      (node (ref "TP2") (pin "TP") (pinfunction "TP_TP") (pintype "input"))
    )
    (net (code "30") (name "Net-(IC3A-+IN)") (class "Default")
      (node (ref "C18") (pin "2") (pinfunction "2_2") (pintype "passive"))
      (node (ref "IC3") (pin "3") (pinfunction "+IN_3") (pintype "input"))
      (node (ref "R22") (pin "2") (pinfunction "2_2") (pintype "passive"))
    )
    (net (code "31") (name "Net-(IC3A--IN)") (class "Default")
      (node (ref "IC3") (pin "1") (pinfunction "OUT_1") (pintype "output"))
      (node (ref "IC3") (pin "2") (pinfunction "-IN_2") (pintype "input"))
      (node (ref "POT_L_OPT") (pin "1") (pinfunction "1_1") (pintype "passive"))
      (node (ref "R23") (pin "2") (pinfunction "2_2") (pintype "passive"))
      (node (ref "TP9") (pin "TP") (pinfunction "TP_TP") (pintype "input"))
    )
    (net (code "32") (name "Net-(IC3B--IN)") (class "Default")
      (node (ref "IC3") (pin "6") (pinfunction "-IN_6") (pintype "input"))
      (node (ref "R21") (pin "1") (pinfunction "1_1") (pintype "passive"))
      (node (ref "R24") (pin "1") (pinfunction "1_1") (pintype "passive"))
      (node (ref "R25") (pin "2") (pinfunction "2_2") (pintype "passive"))
      (node (ref "TP3") (pin "TP") (pinfunction "TP_TP") (pintype "input"))
    )
    (net (code "33") (name "Net-(IC4B-+IN)") (class "Default")
      (node (ref "C24") (pin "1") (pinfunction "1_1") (pintype "passive"))
      (node (ref "IC4") (pin "5") (pinfunction "+IN_5") (pintype "input"))
      (node (ref "R35") (pin "2") (pinfunction "2_2") (pintype "passive"))
    )
    (net (code "34") (name "Net-(IC5A--IN)") (class "Default")
      (node (ref "IC5") (pin "2") (pinfunction "-IN_2") (pintype "input"))
      (node (ref "R36") (pin "2") (pinfunction "2_2") (pintype "passive"))
      (node (ref "R37") (pin "1") (pinfunction "1_1") (pintype "passive"))
    )
    (net (code "35") (name "Net-(IC5A-OUT)") (class "Default")
      (node (ref "IC5") (pin "1") (pinfunction "OUT_1") (pintype "output"))
      (node (ref "POT_SUB_1_OPT") (pin "1") (pinfunction "1_1") (pintype "passive"))
      (node (ref "R37") (pin "2") (pinfunction "2_2") (pintype "passive"))
    )
    (net (code "36") (name "Net-(IC5B--IN)") (class "Default")
      (node (ref "IC5") (pin "6") (pinfunction "-IN_6") (pintype "input"))
      (node (ref "R4") (pin "1") (pinfunction "1_1") (pintype "passive"))
      (node (ref "R5") (pin "2") (pinfunction "2_2") (pintype "passive"))
      (node (ref "TP8") (pin "TP") (pinfunction "TP_TP") (pintype "input"))
    )
    (net (code "37") (name "Net-(IC6A--IN)") (class "Default")
      (node (ref "IC6") (pin "2") (pinfunction "-IN_2") (pintype "input"))
      (node (ref "R42") (pin "1") (pinfunction "1_1") (pintype "passive"))
      (node (ref "R43") (pin "2") (pinfunction "2_2") (pintype "passive"))
      (node (ref "TP11") (pin "TP") (pinfunction "TP_TP") (pintype "input"))
    )
    (net (code "38") (name "Net-(IC6B--IN)") (class "Default")
      (node (ref "IC6") (pin "6") (pinfunction "-IN_6") (pintype "input"))
      (node (ref "R2") (pin "2") (pinfunction "2_2") (pintype "passive"))
      (node (ref "R3") (pin "1") (pinfunction "1_1") (pintype "passive"))
    )
    (net (code "39") (name "Net-(IN1A-KL)") (class "Default")
      (node (ref "IN1") (pin "P$1") (pinfunction "KL_P$1") (pintype "passive"))
      (node (ref "SW1") (pin "1") (pinfunction "S0B_1") (pintype "bidirectional"))
    )
    (net (code "40") (name "Net-(IN1C-KL)") (class "Default")
      (node (ref "IN1") (pin "P$3") (pinfunction "KL_P$3") (pintype "passive"))
      (node (ref "SW1") (pin "12") (pinfunction "S0A_12") (pintype "bidirectional"))
    )
    (net (code "41") (name "Net-(IN2A-KL)") (class "Default")
      (node (ref "IN2") (pin "P$1") (pinfunction "KL_P$1") (pintype "passive"))
      (node (ref "SW1") (pin "5") (pinfunction "S1B_5") (pintype "bidirectional"))
    )
    (net (code "42") (name "Net-(IN2C-KL)") (class "Default")
      (node (ref "IN2") (pin "P$3") (pinfunction "KL_P$3") (pintype "passive"))
      (node (ref "SW1") (pin "14") (pinfunction "S1A_14") (pintype "bidirectional"))
    )
    (net (code "43") (name "Net-(IN3A-KL)") (class "Default")
      (node (ref "IN3") (pin "P$1") (pinfunction "KL_P$1") (pintype "passive"))
      (node (ref "SW1") (pin "2") (pinfunction "S2B_2") (pintype "bidirectional"))
    )
    (net (code "44") (name "Net-(IN3C-KL)") (class "Default")
      (node (ref "IN3") (pin "P$3") (pinfunction "KL_P$3") (pintype "passive"))
      (node (ref "SW1") (pin "15") (pinfunction "S2A_15") (pintype "bidirectional"))
    )
    (net (code "45") (name "Net-(IN4A-KL)") (class "Default")
      (node (ref "IN4") (pin "P$1") (pinfunction "KL_P$1") (pintype "passive"))
      (node (ref "SW1") (pin "4") (pinfunction "S3B_4") (pintype "bidirectional"))
    )
    (net (code "46") (name "Net-(IN4C-KL)") (class "Default")
      (node (ref "IN4") (pin "P$3") (pinfunction "KL_P$3") (pintype "passive"))
      (node (ref "SW1") (pin "11") (pinfunction "S3A_11") (pintype "bidirectional"))
    )
    (net (code "47") (name "Net-(IN5A-KL)") (class "Default")
      (node (ref "IN5") (pin "P$1") (pinfunction "KL_P$1") (pintype "passive"))
      (node (ref "SW2") (pin "5") (pinfunction "S1B_5") (pintype "bidirectional"))
    )
    (net (code "48") (name "Net-(IN5C-KL)") (class "Default")
      (node (ref "IN5") (pin "P$3") (pinfunction "KL_P$3") (pintype "passive"))
      (node (ref "SW2") (pin "14") (pinfunction "S1A_14") (pintype "bidirectional"))
    )
    (net (code "49") (name "Net-(IN6A-KL)") (class "Default")
      (node (ref "IN6") (pin "P$1") (pinfunction "KL_P$1") (pintype "passive"))
      (node (ref "SW2") (pin "2") (pinfunction "S2B_2") (pintype "bidirectional"))
    )
    (net (code "50") (name "Net-(IN6C-KL)") (class "Default")
      (node (ref "IN6") (pin "P$3") (pinfunction "KL_P$3") (pintype "passive"))
      (node (ref "SW2") (pin "15") (pinfunction "S2A_15") (pintype "bidirectional"))
    )
    (net (code "51") (name "Net-(IN7A-KL)") (class "Default")
      (node (ref "IN7") (pin "P$1") (pinfunction "KL_P$1") (pintype "passive"))
      (node (ref "SW2") (pin "4") (pinfunction "S3B_4") (pintype "bidirectional"))
    )
    (net (code "52") (name "Net-(IN7C-KL)") (class "Default")
      (node (ref "IN7") (pin "P$3") (pinfunction "KL_P$3") (pintype "passive"))
      (node (ref "SW2") (pin "11") (pinfunction "S3A_11") (pintype "bidirectional"))
    )
    (net (code "53") (name "Net-(POT1-SCK)") (class "Default")
      (node (ref "POT1") (pin "2") (pinfunction "SCK_2") (pintype "bidirectional"))
      (node (ref "POT2") (pin "2") (pinfunction "SCK_2") (pintype "bidirectional"))
      (node (ref "SPI_CLK") (pin "6") (pinfunction "6_6") (pintype "passive"))
    )
    (net (code "54") (name "Net-(POT1-SI)") (class "Default")
      (node (ref "POT1") (pin "3") (pinfunction "SI_3") (pintype "bidirectional"))
      (node (ref "SPI_CLK") (pin "2") (pinfunction "2_2") (pintype "passive"))
    )
    (net (code "55") (name "Net-(POT1-SO)") (class "Default")
      (node (ref "POT1") (pin "13") (pinfunction "SO_13") (pintype "bidirectional"))
      (node (ref "SPI_CLK") (pin "4") (pinfunction "4_4") (pintype "passive"))
    )
    (net (code "56") (name "Net-(POT1-~{CS})") (class "Default")
      (node (ref "CS") (pin "1") (pinfunction "1_1") (pintype "passive"))
      (node (ref "POT1") (pin "1") (pinfunction "~{CS}_1") (pintype "bidirectional"))
    )
    (net (code "57") (name "Net-(POT2-PA1)") (class "Default")
      (node (ref "C42") (pin "2") (pinfunction "2_2") (pintype "passive"))
      (node (ref "POT2") (pin "7") (pinfunction "PA1_7") (pintype "bidirectional"))
      (node (ref "R16") (pin "1") (pinfunction "1_1") (pintype "passive"))
      (node (ref "R17") (pin "2") (pinfunction "2_2") (pintype "passive"))
      (node (ref "TP1") (pin "TP") (pinfunction "TP_TP") (pintype "input"))
    )
    (net (code "58") (name "Net-(POT2-PW1)") (class "Default")
      (node (ref "C4") (pin "1") (pinfunction "1_1") (pintype "passive"))
      (node (ref "POT2") (pin "6") (pinfunction "PW1_6") (pintype "bidirectional"))
    )
    (net (code "59") (name "Net-(POT2-SI)") (class "Default")
      (node (ref "POT2") (pin "3") (pinfunction "SI_3") (pintype "bidirectional"))
      (node (ref "SPI_CLK") (pin "3") (pinfunction "3_3") (pintype "passive"))
    )
    (net (code "60") (name "Net-(POT2-SO)") (class "Default")
      (node (ref "POT2") (pin "13") (pinfunction "SO_13") (pintype "bidirectional"))
      (node (ref "SPI_CLK") (pin "1") (pinfunction "1_1") (pintype "passive"))
    )
    (net (code "61") (name "Net-(POT2-~{CS})") (class "Default")
      (node (ref "CS") (pin "2") (pinfunction "2_2") (pintype "passive"))
      (node (ref "POT2") (pin "1") (pinfunction "~{CS}_1") (pintype "bidirectional"))
    )
    (net (code "62") (name "Net-(SW1-A0)") (class "Default")
      (node (ref "BIN1") (pin "1") (pinfunction "1_1") (pintype "passive"))
      (node (ref "SW1") (pin "10") (pinfunction "A0_10") (pintype "input"))
    )
    (net (code "63") (name "Net-(SW1-A1)") (class "Default")
      (node (ref "BIN1") (pin "2") (pinfunction "2_2") (pintype "passive"))
      (node (ref "SW1") (pin "9") (pinfunction "A1_9") (pintype "input"))
    )
    (net (code "64") (name "Net-(SW2-A0)") (class "Default")
      (node (ref "BIN2") (pin "1") (pinfunction "1_1") (pintype "passive"))
      (node (ref "SW2") (pin "10") (pinfunction "A0_10") (pintype "input"))
    )
    (net (code "65") (name "Net-(SW2-A1)") (class "Default")
      (node (ref "BIN2") (pin "2") (pinfunction "2_2") (pintype "passive"))
      (node (ref "SW2") (pin "9") (pinfunction "A1_9") (pintype "input"))
    )
    (net (code "66") (name "R1") (class "Default")
      (node (ref "SW1") (pin "13") (pinfunction "DA_13") (pintype "bidirectional"))
      (node (ref "SW2") (pin "12") (pinfunction "S0A_12") (pintype "bidirectional"))
      (node (ref "TP4") (pin "TP") (pinfunction "TP_TP") (pintype "input"))
    )
    (net (code "67") (name "R2") (class "Default")
      (node (ref "R19") (pin "2") (pinfunction "2_2") (pintype "passive"))
      (node (ref "R2_PIN") (pin "1") (pinfunction "1_1") (pintype "passive"))
      (node (ref "SW2") (pin "13") (pinfunction "DA_13") (pintype "bidirectional"))
    )
    (net (code "68") (name "R3") (class "Default")
      (node (ref "C5") (pin "2") (pinfunction "2_2") (pintype "passive"))
      (node (ref "POT1") (pin "8") (pinfunction "PA0_8") (pintype "bidirectional"))
      (node (ref "R7") (pin "1") (pinfunction "1_1") (pintype "passive"))
      (node (ref "R9") (pin "2") (pinfunction "2_2") (pintype "passive"))
    )
    (net (code "69") (name "R4") (class "Default")
      (node (ref "C7") (pin "1") (pinfunction "1_1") (pintype "passive"))
      (node (ref "POT1") (pin "9") (pinfunction "PW0_9") (pintype "bidirectional"))
    )
    (net (code "70") (name "R5") (class "Default")
      (node (ref "C7") (pin "2") (pinfunction "2_2") (pintype "passive"))
      (node (ref "R10") (pin "2") (pinfunction "2_2") (pintype "passive"))
      (node (ref "R4") (pin "2") (pinfunction "2_2") (pintype "passive"))
      (node (ref "TP12") (pin "TP") (pinfunction "TP_TP") (pintype "input"))
    )
    (net (code "71") (name "R6") (class "Default")
      (node (ref "IC5") (pin "7") (pinfunction "OUT_7") (pintype "output"))
      (node (ref "R5") (pin "1") (pinfunction "1_1") (pintype "passive"))
      (node (ref "R_FILTER_JPR") (pin "2") (pinfunction "2_2") (pintype "passive"))
    )
    (net (code "72") (name "R7") (class "Default")
      (node (ref "C5") (pin "1") (pinfunction "1_1") (pintype "passive"))
      (node (ref "IC2") (pin "7") (pinfunction "OUT_7") (pintype "output"))
      (node (ref "R18") (pin "1") (pinfunction "1_1") (pintype "passive"))
      (node (ref "R28") (pin "2") (pinfunction "2_2") (pintype "passive"))
    )
    (net (code "73") (name "R_IN") (class "Default")
      (node (ref "C17") (pin "1") (pinfunction "1_1") (pintype "passive"))
      (node (ref "R_FILTER_JPR") (pin "3") (pinfunction "3_3") (pintype "passive"))
    )
    (net (code "74") (name "R_OUT") (class "Default")
      (node (ref "OUTPUT") (pin "8") (pinfunction "8_8") (pintype "passive"))
      (node (ref "POT_R_OPT") (pin "2") (pinfunction "2_2") (pintype "passive"))
      (node (ref "R_FILTER_JPR") (pin "1") (pinfunction "1_1") (pintype "passive"))
    )
    (net (code "75") (name "SUB1") (class "Default")
      (node (ref "IC1") (pin "6") (pinfunction "-IN_6") (pintype "input"))
      (node (ref "R11") (pin "2") (pinfunction "2_2") (pintype "passive"))
      (node (ref "R27") (pin "1") (pinfunction "1_1") (pintype "passive"))
      (node (ref "R28") (pin "1") (pinfunction "1_1") (pintype "passive"))
      (node (ref "TP7") (pin "TP") (pinfunction "TP_TP") (pintype "input"))
    )
    (net (code "76") (name "SUB2") (class "Default")
      (node (ref "ADD") (pin "2") (pinfunction "2_2") (pintype "passive"))
      (node (ref "IC1") (pin "7") (pinfunction "OUT_7") (pintype "output"))
      (node (ref "R11") (pin "1") (pinfunction "1_1") (pintype "passive"))
    )
    (net (code "77") (name "SUB3") (class "Default")
      (node (ref "C43") (pin "2") (pinfunction "2_2") (pintype "passive"))
      (node (ref "POT2") (pin "8") (pinfunction "PA0_8") (pintype "bidirectional"))
      (node (ref "R12") (pin "1") (pinfunction "1_1") (pintype "passive"))
      (node (ref "R13") (pin "2") (pinfunction "2_2") (pintype "passive"))
      (node (ref "TP6") (pin "TP") (pinfunction "TP_TP") (pintype "input"))
    )
    (net (code "78") (name "SUB4") (class "Default")
      (node (ref "C11") (pin "1") (pinfunction "1_1") (pintype "passive"))
      (node (ref "POT2") (pin "9") (pinfunction "PW0_9") (pintype "bidirectional"))
    )
    (net (code "79") (name "SUB5") (class "Default")
      (node (ref "C11") (pin "2") (pinfunction "2_2") (pintype "passive"))
      (node (ref "IC6") (pin "5") (pinfunction "+IN_5") (pintype "input"))
      (node (ref "R15") (pin "2") (pinfunction "2_2") (pintype "passive"))
    )
    (net (code "80") (name "SUB_IN") (class "Default")
      (node (ref "IC6") (pin "7") (pinfunction "OUT_7") (pintype "output"))
      (node (ref "R3") (pin "2") (pinfunction "2_2") (pintype "passive"))
      (node (ref "R34") (pin "2") (pinfunction "2_2") (pintype "passive"))
    )
    (net (code "81") (name "SUB_PHASE") (class "Default")
      (node (ref "C23") (pin "1") (pinfunction "1_1") (pintype "passive"))
      (node (ref "IC4") (pin "6") (pinfunction "-IN_6") (pintype "input"))
      (node (ref "IC4") (pin "7") (pinfunction "OUT_7") (pintype "output"))
      (node (ref "POT_SUB_2_OPT") (pin "1") (pinfunction "1_1") (pintype "passive"))
      (node (ref "R36") (pin "1") (pinfunction "1_1") (pintype "passive"))
    )
  )
)
